# nRF24LU1.net
KiCad netlist of a schematic drawn in EAGLE
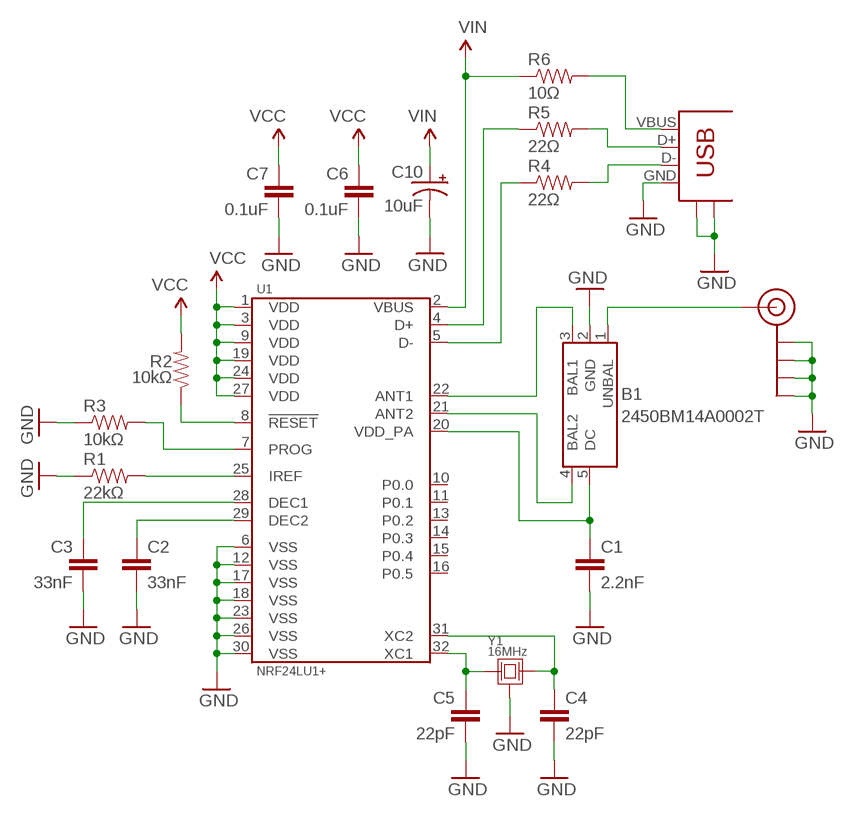
[diagram p0: schematic, sheet 1]

(export (version "E")
  (design (tool "Eeschema 10.0.6"))
  (components
    (comp (ref "B1")
      (value "2450BM14A0002T")
      (footprint "eagle-import:BALUN-0603")
      (libsource (lib "eagle-import") (part "2450BM14A0002T"))
    )
    (comp (ref "C1")
      (value "2.2nF")
      (footprint "eagle-import:0402-CAP")
      (libsource (lib "eagle-import") (part "CAP0402-CAP"))
    )
    (comp (ref "C2")
      (value "33nF")
      (footprint "eagle-import:0402-CAP")
      (libsource (lib "eagle-import") (part "CAP0402-CAP"))
    )
    (comp (ref "C3")
      (value "33nF")
      (footprint "eagle-import:0402-CAP")
      (libsource (lib "eagle-import") (part "CAP0402-CAP"))
    )
    (comp (ref "C4")
      (value "22pF")
      (footprint "eagle-import:0402-CAP")
      (libsource (lib "eagle-import") (part "CAP0402-CAP"))
    )
    (comp (ref "C5")
      (value "22pF")
      (footprint "eagle-import:0402-CAP")
      (libsource (lib "eagle-import") (part "CAP0402-CAP"))
    )
    (comp (ref "C6")
      (value "0.1uF")
      (footprint "eagle-import:0402-CAP")
      (libsource (lib "eagle-import") (part "CAP0402-CAP"))
    )
    (comp (ref "C7")
      (value "0.1uF")
      (footprint "eagle-import:0402-CAP")
      (libsource (lib "eagle-import") (part "CAP0402-CAP"))
    )
    (comp (ref "C10")
      (value "10uF")
      (footprint "eagle-import:0805-CAP_POL")
      (libsource (lib "eagle-import") (part "CAP_POL0805"))
    )
    (comp (ref "J$1")
      (value "SMA_EDGE")
      (footprint "eagle-import:SMA-EDGE")
      (libsource (lib "eagle-import") (part "SMA_EDGE"))
    )
    (comp (ref "J1")
      (value "USB+SHIELD-A-H")
      (footprint "eagle-import:USB-A-H")
      (libsource (lib "eagle-import") (part "USB+SHIELD-A-H"))
    )
    (comp (ref "R1")
      (value "22kΩ")
      (footprint "eagle-import:0402-RES")
      (libsource (lib "eagle-import") (part "RESISTOR0402-RES"))
    )
    (comp (ref "R2")
      (value "10kΩ")
      (footprint "eagle-import:0402-RES")
      (libsource (lib "eagle-import") (part "RESISTOR0402-RES"))
    )
    (comp (ref "R3")
      (value "10kΩ")
      (footprint "eagle-import:0402-RES")
      (libsource (lib "eagle-import") (part "RESISTOR0402-RES"))
    )
    (comp (ref "R4")
      (value "22Ω")
      (footprint "eagle-import:0402-RES")
      (libsource (lib "eagle-import") (part "RESISTOR0402-RES"))
    )
    (comp (ref "R5")
      (value "22Ω")
      (footprint "eagle-import:0402-RES")
      (libsource (lib "eagle-import") (part "RESISTOR0402-RES"))
    )
    (comp (ref "R6")
      (value "10Ω")
      (footprint "eagle-import:0402-RES")
      (libsource (lib "eagle-import") (part "RESISTOR0402-RES"))
    )
    (comp (ref "U1")
      (value "NRF24LU1+")
      (footprint "eagle-import:QFN-32")
      (libsource (lib "eagle-import") (part "NRF24LU1+"))
    )
    (comp (ref "Y1")
      (value "16MHz")
      (footprint "eagle-import:FA-238")
      (libsource (lib "eagle-import") (part "CRYSTAL-3.2X2.5"))
    )
  )
  (nets
    (net (code "1") (name "GND") (class "Default")
      (node (ref "B1") (pin "2") (pinfunction "GND_2") (pintype "bidirectional"))
      (node (ref "C1") (pin "2") (pinfunction "2_2") (pintype "passive"))
      (node (ref "C10") (pin "C") (pinfunction "-_C") (pintype "passive"))
      (node (ref "C2") (pin "2") (pinfunction "2_2") (pintype "passive"))
      (node (ref "C3") (pin "2") (pinfunction "2_2") (pintype "passive"))
      (node (ref "C4") (pin "2") (pinfunction "2_2") (pintype "passive"))
      (node (ref "C5") (pin "2") (pinfunction "2_2") (pintype "passive"))
      (node (ref "C6") (pin "2") (pinfunction "2_2") (pintype "passive"))
      (node (ref "C7") (pin "2") (pinfunction "2_2") (pintype "passive"))
      (node (ref "J$1") (pin "GND@0") (pinfunction "GND_GND@0") (pintype "bidirectional"))
      (node (ref "J$1") (pin "GND@1") (pinfunction "GND_GND@1") (pintype "bidirectional"))
      (node (ref "J$1") (pin "GND@2") (pinfunction "GND_GND@2") (pintype "bidirectional"))
      (node (ref "J$1") (pin "GND@3") (pinfunction "GND_GND@3") (pintype "bidirectional"))
      (node (ref "J1") (pin "GND") (pinfunction "GND_GND") (pintype "bidirectional"))
      (node (ref "J1") (pin "GND2") (pinfunction "S1_GND2") (pintype "bidirectional"))
      (node (ref "J1") (pin "GND3") (pinfunction "S2_GND3") (pintype "bidirectional"))
      (node (ref "R1") (pin "1") (pinfunction "1_1") (pintype "passive"))
      (node (ref "R3") (pin "1") (pinfunction "1_1") (pintype "passive"))
      (node (ref "U1") (pin "12") (pinfunction "VSS_12") (pintype "bidirectional"))
      (node (ref "U1") (pin "17") (pinfunction "VSS_17") (pintype "bidirectional"))
      (node (ref "U1") (pin "18") (pinfunction "VSS_18") (pintype "bidirectional"))
      (node (ref "U1") (pin "23") (pinfunction "VSS_23") (pintype "bidirectional"))
      (node (ref "U1") (pin "26") (pinfunction "VSS_26") (pintype "bidirectional"))
      (node (ref "U1") (pin "30") (pinfunction "VSS_30") (pintype "bidirectional"))
      (node (ref "U1") (pin "6") (pinfunction "VSS_6") (pintype "bidirectional"))
      (node (ref "Y1") (pin "2") (pinfunction "GND_2") (pintype "bidirectional"))
      (node (ref "Y1") (pin "4") (pinfunction "GND_4") (pintype "bidirectional"))
    )
    (net (code "2") (name "Net-(B1-BAL1)") (class "Default")
      (node (ref "B1") (pin "3") (pinfunction "BAL1_3") (pintype "bidirectional"))
      (node (ref "U1") (pin "22") (pinfunction "ANT1_22") (pintype "bidirectional"))
    )
    (net (code "3") (name "Net-(B1-BAL2)") (class "Default")
      (node (ref "B1") (pin "4") (pinfunction "BAL2_4") (pintype "bidirectional"))
      (node (ref "U1") (pin "21") (pinfunction "ANT2_21") (pintype "bidirectional"))
    )
    (net (code "4") (name "Net-(B1-DC)") (class "Default")
      (node (ref "B1") (pin "5") (pinfunction "DC_5") (pintype "bidirectional"))
      (node (ref "C1") (pin "1") (pinfunction "1_1") (pintype "passive"))
      (node (ref "U1") (pin "20") (pinfunction "VDD_PA_20") (pintype "bidirectional"))
    )
    (net (code "5") (name "Net-(B1-UNBAL)") (class "Default")
      (node (ref "B1") (pin "1") (pinfunction "UNBAL_1") (pintype "bidirectional"))
      (node (ref "J$1") (pin "SIG") (pinfunction "SIGNAL_SIG") (pintype "bidirectional"))
    )
    (net (code "6") (name "Net-(J1-PadD+)") (class "Default")
      (node (ref "J1") (pin "D+") (pinfunction "D+_D+") (pintype "bidirectional"))
      (node (ref "R5") (pin "2") (pinfunction "2_2") (pintype "passive"))
    )
    (net (code "7") (name "Net-(J1-PadD-)") (class "Default")
      (node (ref "J1") (pin "D-") (pinfunction "D-_D-") (pintype "bidirectional"))
      (node (ref "R4") (pin "2") (pinfunction "2_2") (pintype "passive"))
    )
    (net (code "8") (name "Net-(J1-PadVBUS)") (class "Default")
      (node (ref "J1") (pin "VBUS") (pinfunction "VBUS_VBUS") (pintype "bidirectional"))
      (node (ref "R6") (pin "2") (pinfunction "2_2") (pintype "passive"))
    )
    (net (code "9") (name "Net-(U1-D+)") (class "Default")
      (node (ref "R5") (pin "1") (pinfunction "1_1") (pintype "passive"))
      (node (ref "U1") (pin "4") (pinfunction "D+_4") (pintype "bidirectional"))
    )
    (net (code "10") (name "Net-(U1-D-)") (class "Default")
      (node (ref "R4") (pin "1") (pinfunction "1_1") (pintype "passive"))
      (node (ref "U1") (pin "5") (pinfunction "D-_5") (pintype "bidirectional"))
    )
    (net (code "11") (name "Net-(U1-DEC1)") (class "Default")
      (node (ref "C3") (pin "1") (pinfunction "1_1") (pintype "passive"))
      (node (ref "U1") (pin "28") (pinfunction "DEC1_28") (pintype "bidirectional"))
    )
    (net (code "12") (name "Net-(U1-DEC2)") (class "Default")
      (node (ref "C2") (pin "1") (pinfunction "1_1") (pintype "passive"))
      (node (ref "U1") (pin "29") (pinfunction "DEC2_29") (pintype "bidirectional"))
    )
    (net (code "13") (name "Net-(U1-IREF)") (class "Default")
      (node (ref "R1") (pin "2") (pinfunction "2_2") (pintype "passive"))
      (node (ref "U1") (pin "25") (pinfunction "IREF_25") (pintype "bidirectional"))
    )
    (net (code "14") (name "Net-(U1-PROG)") (class "Default")
      (node (ref "R3") (pin "2") (pinfunction "2_2") (pintype "passive"))
      (node (ref "U1") (pin "7") (pinfunction "PROG_7") (pintype "bidirectional"))
    )
    (net (code "15") (name "Net-(U1-XC1)") (class "Default")
      (node (ref "C5") (pin "1") (pinfunction "1_1") (pintype "passive"))
      (node (ref "U1") (pin "32") (pinfunction "XC1_32") (pintype "bidirectional"))
      (node (ref "Y1") (pin "1") (pinfunction "1_1") (pintype "bidirectional"))
    )
    (net (code "16") (name "Net-(U1-XC2)") (class "Default")
      (node (ref "C4") (pin "1") (pinfunction "1_1") (pintype "passive"))
      (node (ref "U1") (pin "31") (pinfunction "XC2_31") (pintype "bidirectional"))
      (node (ref "Y1") (pin "3") (pinfunction "2_3") (pintype "bidirectional"))
    )
    (net (code "17") (name "Net-(U1-~{RESET})") (class "Default")
      (node (ref "R2") (pin "1") (pinfunction "1_1") (pintype "passive"))
      (node (ref "U1") (pin "8") (pinfunction "~{RESET}_8") (pintype "bidirectional"))
    )
    (net (code "18") (name "VCC") (class "Default")
      (node (ref "C6") (pin "1") (pinfunction "1_1") (pintype "passive"))
      (node (ref "C7") (pin "1") (pinfunction "1_1") (pintype "passive"))
      (node (ref "R2") (pin "2") (pinfunction "2_2") (pintype "passive"))
      (node (ref "U1") (pin "1") (pinfunction "VDD_1") (pintype "bidirectional"))
      (node (ref "U1") (pin "19") (pinfunction "VDD_19") (pintype "bidirectional"))
      (node (ref "U1") (pin "24") (pinfunction "VDD_24") (pintype "bidirectional"))
      (node (ref "U1") (pin "27") (pinfunction "VDD_27") (pintype "bidirectional"))
      (node (ref "U1") (pin "3") (pinfunction "VDD_3") (pintype "bidirectional"))
      (node (ref "U1") (pin "9") (pinfunction "VDD_9") (pintype "bidirectional"))
    )
    (net (code "19") (name "VIN") (class "Default")
      (node (ref "C10") (pin "A") (pinfunction "+_A") (pintype "passive"))
      (node (ref "R6") (pin "1") (pinfunction "1_1") (pintype "passive"))
      (node (ref "U1") (pin "2") (pinfunction "VBUS_2") (pintype "bidirectional"))
    )
    (net (code "20") (name "unconnected-(U1-P0.0-Pad10)") (class "Default")
      (node (ref "U1") (pin "10") (pinfunction "P0.0_10") (pintype "bidirectional"))
    )
    (net (code "21") (name "unconnected-(U1-P0.1-Pad11)") (class "Default")
      (node (ref "U1") (pin "11") (pinfunction "P0.1_11") (pintype "bidirectional"))
    )
    (net (code "22") (name "unconnected-(U1-P0.2-Pad13)") (class "Default")
      (node (ref "U1") (pin "13") (pinfunction "P0.2_13") (pintype "bidirectional"))
    )
    (net (code "23") (name "unconnected-(U1-P0.3-Pad14)") (class "Default")
      (node (ref "U1") (pin "14") (pinfunction "P0.3_14") (pintype "bidirectional"))
    )
    (net (code "24") (name "unconnected-(U1-P0.4-Pad15)") (class "Default")
      (node (ref "U1") (pin "15") (pinfunction "P0.4_15") (pintype "bidirectional"))
    )
    (net (code "25") (name "unconnected-(U1-P0.5-Pad16)") (class "Default")
      (node (ref "U1") (pin "16") (pinfunction "P0.5_16") (pintype "bidirectional"))
    )
  )
)
